# RGB-light.net
KiCad netlist of a schematic drawn in EAGLE
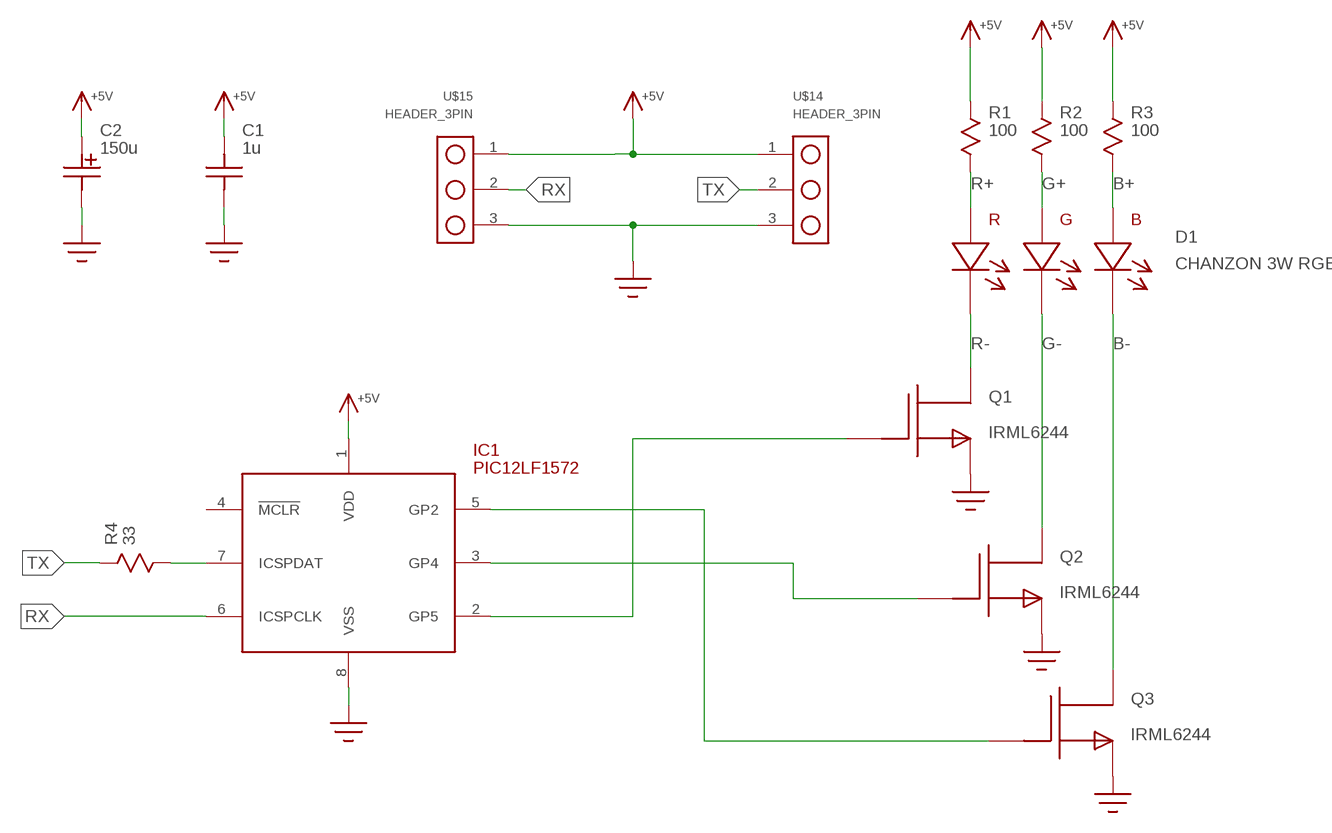
[diagram p0: schematic, sheet 1]

(export (version "E")
  (design (tool "Eeschema 10.0.6"))
  (components
    (comp (ref "C1")
      (value "1u")
      (footprint "eagle-import:C0603")
      (libsource (lib "eagle-import") (part "C0603"))
    )
    (comp (ref "C2")
      (value "150u")
      (footprint "eagle-import:C-TANTALUM-CODE-C")
      (libsource (lib "eagle-import") (part "C-POLARIZEDTANTALUM-C"))
    )
    (comp (ref "D1")
      (value "CHANZON 3W RGB")
      (footprint "eagle-import:LED_3W_RGB")
      (libsource (lib "eagle-import") (part "LED-RGB-3W"))
    )
    (comp (ref "IC1")
      (value "PIC12LF1572")
      (footprint "eagle-import:SOIC8")
      (libsource (lib "eagle-import") (part "PIC12LF1571"))
    )
    (comp (ref "Q1")
      (value "IRML6244")
      (footprint "eagle-import:SOT-23")
      (libsource (lib "eagle-import") (part "ZXMN3B01FSOT23"))
    )
    (comp (ref "Q2")
      (value "IRML6244")
      (footprint "eagle-import:SOT-23")
      (libsource (lib "eagle-import") (part "ZXMN3B01FSOT23"))
    )
    (comp (ref "Q3")
      (value "IRML6244")
      (footprint "eagle-import:SOT-23")
      (libsource (lib "eagle-import") (part "ZXMN3B01FSOT23"))
    )
    (comp (ref "R1")
      (value "100")
      (footprint "eagle-import:R1206")
      (libsource (lib "eagle-import") (part "R1206"))
    )
    (comp (ref "R2")
      (value "100")
      (footprint "eagle-import:R1206")
      (libsource (lib "eagle-import") (part "R1206"))
    )
    (comp (ref "R3")
      (value "100")
      (footprint "eagle-import:R1206")
      (libsource (lib "eagle-import") (part "R1206"))
    )
    (comp (ref "R4")
      (value "33")
      (footprint "eagle-import:R0603")
      (libsource (lib "eagle-import") (part "R0603"))
    )
    (comp (ref "U$14")
      (value "HEADER_3PIN")
      (footprint "eagle-import:HEADER_3PIN")
      (libsource (lib "eagle-import") (part "HEADER_3PIN"))
    )
    (comp (ref "U$15")
      (value "HEADER_3PIN")
      (footprint "eagle-import:HEADER_3PIN")
      (libsource (lib "eagle-import") (part "HEADER_3PIN"))
    )
  )
  (nets
    (net (code "1") (name "+5V") (class "Default")
      (node (ref "C1") (pin "P$2") (pinfunction "P$2_P$2") (pintype "bidirectional"))
      (node (ref "C2") (pin "+") (pinfunction "+_+") (pintype "bidirectional"))
      (node (ref "IC1") (pin "1") (pinfunction "VDD_1") (pintype "bidirectional"))
      (node (ref "R1") (pin "P$1") (pinfunction "P$3_P$1") (pintype "bidirectional"))
      (node (ref "R2") (pin "P$1") (pinfunction "P$3_P$1") (pintype "bidirectional"))
      (node (ref "R3") (pin "P$1") (pinfunction "P$3_P$1") (pintype "bidirectional"))
      (node (ref "U$14") (pin "1") (pinfunction "1_1") (pintype "bidirectional"))
      (node (ref "U$15") (pin "1") (pinfunction "1_1") (pintype "bidirectional"))
    )
    (net (code "2") (name "/B+") (class "Default")
      (node (ref "D1") (pin "B+") (pinfunction "B-A_B+") (pintype "bidirectional"))
      (node (ref "R3") (pin "P$2") (pinfunction "P$4_P$2") (pintype "bidirectional"))
    )
    (net (code "3") (name "/B-") (class "Default")
      (node (ref "D1") (pin "B-") (pinfunction "B-C_B-") (pintype "bidirectional"))
      (node (ref "Q3") (pin "3") (pinfunction "D_3") (pintype "bidirectional"))
    )
    (net (code "4") (name "/G+") (class "Default")
      (node (ref "D1") (pin "G+") (pinfunction "G-A_G+") (pintype "bidirectional"))
      (node (ref "R2") (pin "P$2") (pinfunction "P$4_P$2") (pintype "bidirectional"))
    )
    (net (code "5") (name "/G-") (class "Default")
      (node (ref "D1") (pin "G-") (pinfunction "G-C_G-") (pintype "bidirectional"))
      (node (ref "Q2") (pin "3") (pinfunction "D_3") (pintype "bidirectional"))
    )
    (net (code "6") (name "/R+") (class "Default")
      (node (ref "D1") (pin "R+") (pinfunction "R-A_R+") (pintype "bidirectional"))
      (node (ref "R1") (pin "P$2") (pinfunction "P$4_P$2") (pintype "bidirectional"))
    )
    (net (code "7") (name "/R-") (class "Default")
      (node (ref "D1") (pin "R-") (pinfunction "R-C_R-") (pintype "bidirectional"))
      (node (ref "Q1") (pin "3") (pinfunction "D_3") (pintype "bidirectional"))
    )
    (net (code "8") (name "GND") (class "Default")
      (node (ref "C1") (pin "P$1") (pinfunction "P$1_P$1") (pintype "bidirectional"))
      (node (ref "C2") (pin "-") (pinfunction "-_-") (pintype "bidirectional"))
      (node (ref "IC1") (pin "8") (pinfunction "VSS_8") (pintype "bidirectional"))
      (node (ref "Q1") (pin "2") (pinfunction "S_2") (pintype "bidirectional"))
      (node (ref "Q2") (pin "2") (pinfunction "S_2") (pintype "bidirectional"))
      (node (ref "Q3") (pin "2") (pinfunction "S_2") (pintype "bidirectional"))
      (node (ref "U$14") (pin "3") (pinfunction "3_3") (pintype "bidirectional"))
      (node (ref "U$15") (pin "3") (pinfunction "3_3") (pintype "bidirectional"))
    )
    (net (code "9") (name "Net-(IC1-GP2)") (class "Default")
      (node (ref "IC1") (pin "5") (pinfunction "GP2_5") (pintype "bidirectional"))
      (node (ref "Q3") (pin "1") (pinfunction "G_1") (pintype "bidirectional"))
    )
    (net (code "10") (name "Net-(IC1-GP4)") (class "Default")
      (node (ref "IC1") (pin "3") (pinfunction "GP4_3") (pintype "bidirectional"))
      (node (ref "Q2") (pin "1") (pinfunction "G_1") (pintype "bidirectional"))
    )
    (net (code "11") (name "Net-(IC1-GP5)") (class "Default")
      (node (ref "IC1") (pin "2") (pinfunction "GP5_2") (pintype "bidirectional"))
      (node (ref "Q1") (pin "1") (pinfunction "G_1") (pintype "bidirectional"))
    )
    (net (code "12") (name "Net-(IC1-ICSPDAT)") (class "Default")
      (node (ref "IC1") (pin "7") (pinfunction "ICSPDAT_7") (pintype "bidirectional"))
      (node (ref "R4") (pin "P$2") (pinfunction "P$4_P$2") (pintype "bidirectional"))
    )
    (net (code "13") (name "RX") (class "Default")
      (node (ref "IC1") (pin "6") (pinfunction "ICSPCLK_6") (pintype "bidirectional"))
      (node (ref "U$15") (pin "2") (pinfunction "2_2") (pintype "bidirectional"))
    )
    (net (code "14") (name "TX") (class "Default")
      (node (ref "R4") (pin "P$1") (pinfunction "P$3_P$1") (pintype "bidirectional"))
      (node (ref "U$14") (pin "2") (pinfunction "2_2") (pintype "bidirectional"))
    )
    (net (code "15") (name "unconnected-(IC1-~{MCLR}-Pad4)") (class "Default")
      (node (ref "IC1") (pin "4") (pinfunction "~{MCLR}_4") (pintype "bidirectional"))
    )
  )
)
